# Sheet1.net
KiCad netlist of a schematic drawn in Altium Designer
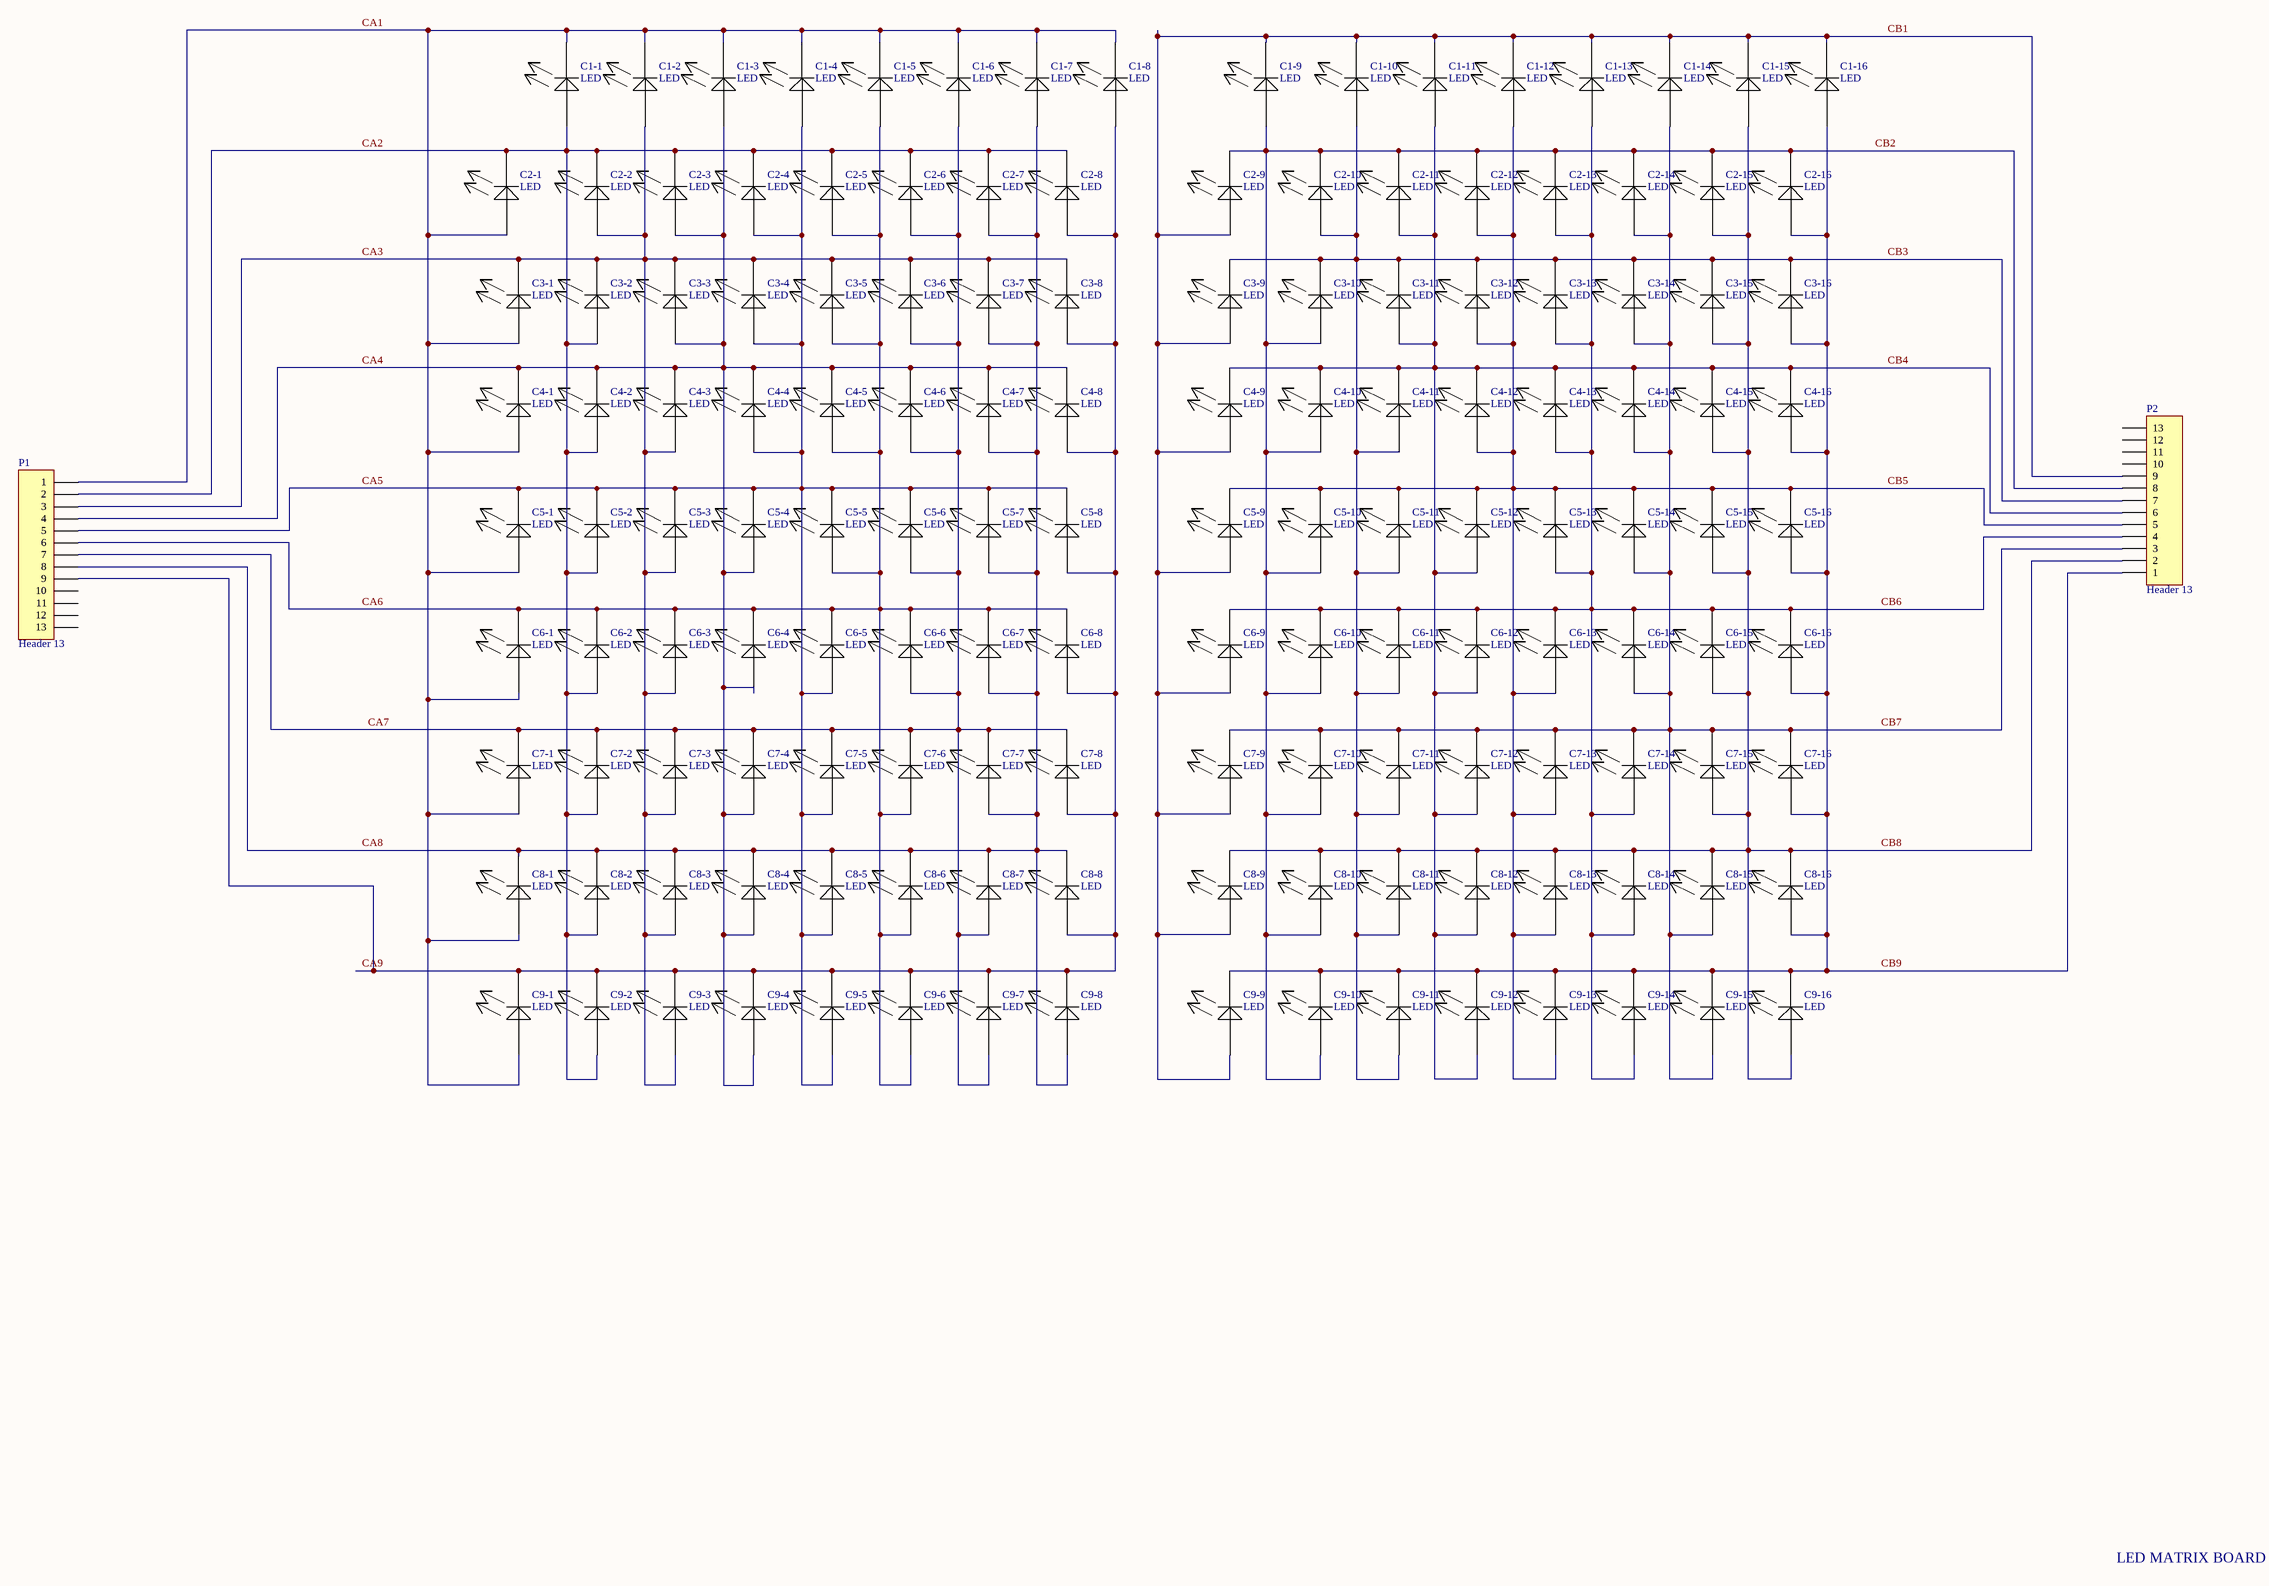
[diagram p0: Sheet1.SchDoc]

(export (version "E")
  (design (tool "Eeschema 10.0.6"))
  (components
    (comp (ref "C1-1") (value "LED") (footprint "LED 0603(2)") (libsource (lib "LEDs") (part "LED")))
    (comp (ref "C1-2") (value "LED") (footprint "LED 0603(2)") (libsource (lib "LEDs") (part "LED")))
    (comp (ref "C1-3") (value "LED") (footprint "LED 0603(2)") (libsource (lib "LEDs") (part "LED")))
    (comp (ref "C1-4") (value "LED") (footprint "LED 0603(2)") (libsource (lib "LEDs") (part "LED")))
    (comp (ref "C1-5") (value "LED") (footprint "LED 0603(2)") (libsource (lib "LEDs") (part "LED")))
    (comp (ref "C1-6") (value "LED") (footprint "LED 0603(2)") (libsource (lib "LEDs") (part "LED")))
    (comp (ref "C1-7") (value "LED") (footprint "LED 0603(2)") (libsource (lib "LEDs") (part "LED")))
    (comp (ref "C1-8") (value "LED") (footprint "LED 0603(2)") (libsource (lib "LEDs") (part "LED")))
    (comp (ref "C1-9") (value "LED") (footprint "LED 0603(2)") (libsource (lib "LEDs") (part "LED")))
    (comp (ref "C1-10") (value "LED") (footprint "LED 0603(2)") (libsource (lib "LEDs") (part "LED")))
    (comp (ref "C1-11") (value "LED") (footprint "LED 0603(2)") (libsource (lib "LEDs") (part "LED")))
    (comp (ref "C1-12") (value "LED") (footprint "LED 0603(2)") (libsource (lib "LEDs") (part "LED")))
    (comp (ref "C1-13") (value "LED") (footprint "LED 0603(2)") (libsource (lib "LEDs") (part "LED")))
    (comp (ref "C1-14") (value "LED") (footprint "LED 0603(2)") (libsource (lib "LEDs") (part "LED")))
    (comp (ref "C1-15") (value "LED") (footprint "LED 0603(2)") (libsource (lib "LEDs") (part "LED")))
    (comp (ref "C1-16") (value "LED") (footprint "LED 0603(2)") (libsource (lib "LEDs") (part "LED")))
    (comp (ref "C2-1") (value "LED") (footprint "LED 0603(2)") (libsource (lib "LEDs") (part "LED")))
    (comp (ref "C2-2") (value "LED") (footprint "LED 0603(2)") (libsource (lib "LEDs") (part "LED")))
    (comp (ref "C2-3") (value "LED") (footprint "LED 0603(2)") (libsource (lib "LEDs") (part "LED")))
    (comp (ref "C2-4") (value "LED") (footprint "LED 0603(2)") (libsource (lib "LEDs") (part "LED")))
    (comp (ref "C2-5") (value "LED") (footprint "LED 0603(2)") (libsource (lib "LEDs") (part "LED")))
    (comp (ref "C2-6") (value "LED") (footprint "LED 0603(2)") (libsource (lib "LEDs") (part "LED")))
    (comp (ref "C2-7") (value "LED") (footprint "LED 0603(2)") (libsource (lib "LEDs") (part "LED")))
    (comp (ref "C2-8") (value "LED") (footprint "LED 0603(2)") (libsource (lib "LEDs") (part "LED")))
    (comp (ref "C2-9") (value "LED") (footprint "LED 0603(2)") (libsource (lib "LEDs") (part "LED")))
    (comp (ref "C2-10") (value "LED") (footprint "LED 0603(2)") (libsource (lib "LEDs") (part "LED")))
    (comp (ref "C2-11") (value "LED") (footprint "LED 0603(2)") (libsource (lib "LEDs") (part "LED")))
    (comp (ref "C2-12") (value "LED") (footprint "LED 0603(2)") (libsource (lib "LEDs") (part "LED")))
    (comp (ref "C2-13") (value "LED") (footprint "LED 0603(2)") (libsource (lib "LEDs") (part "LED")))
    (comp (ref "C2-14") (value "LED") (footprint "LED 0603(2)") (libsource (lib "LEDs") (part "LED")))
    (comp (ref "C2-15") (value "LED") (footprint "LED 0603(2)") (libsource (lib "LEDs") (part "LED")))
    (comp (ref "C2-16") (value "LED") (footprint "LED 0603(2)") (libsource (lib "LEDs") (part "LED")))
    (comp (ref "C3-1") (value "LED") (footprint "LED 0603(2)") (libsource (lib "LEDs") (part "LED")))
    (comp (ref "C3-2") (value "LED") (footprint "LED 0603(2)") (libsource (lib "LEDs") (part "LED")))
    (comp (ref "C3-3") (value "LED") (footprint "LED 0603(2)") (libsource (lib "LEDs") (part "LED")))
    (comp (ref "C3-4") (value "LED") (footprint "LED 0603(2)") (libsource (lib "LEDs") (part "LED")))
    (comp (ref "C3-5") (value "LED") (footprint "LED 0603(2)") (libsource (lib "LEDs") (part "LED")))
    (comp (ref "C3-6") (value "LED") (footprint "LED 0603(2)") (libsource (lib "LEDs") (part "LED")))
    (comp (ref "C3-7") (value "LED") (footprint "LED 0603(2)") (libsource (lib "LEDs") (part "LED")))
    (comp (ref "C3-8") (value "LED") (footprint "LED 0603(2)") (libsource (lib "LEDs") (part "LED")))
    (comp (ref "C3-9") (value "LED") (footprint "LED 0603(2)") (libsource (lib "LEDs") (part "LED")))
    (comp (ref "C3-10") (value "LED") (footprint "LED 0603(2)") (libsource (lib "LEDs") (part "LED")))
    (comp (ref "C3-11") (value "LED") (footprint "LED 0603(2)") (libsource (lib "LEDs") (part "LED")))
    (comp (ref "C3-12") (value "LED") (footprint "LED 0603(2)") (libsource (lib "LEDs") (part "LED")))
    (comp (ref "C3-13") (value "LED") (footprint "LED 0603(2)") (libsource (lib "LEDs") (part "LED")))
    (comp (ref "C3-14") (value "LED") (footprint "LED 0603(2)") (libsource (lib "LEDs") (part "LED")))
    (comp (ref "C3-15") (value "LED") (footprint "LED 0603(2)") (libsource (lib "LEDs") (part "LED")))
    (comp (ref "C3-16") (value "LED") (footprint "LED 0603(2)") (libsource (lib "LEDs") (part "LED")))
    (comp (ref "C4-1") (value "LED") (footprint "LED 0603(2)") (libsource (lib "LEDs") (part "LED")))
    (comp (ref "C4-2") (value "LED") (footprint "LED 0603(2)") (libsource (lib "LEDs") (part "LED")))
    (comp (ref "C4-3") (value "LED") (footprint "LED 0603(2)") (libsource (lib "LEDs") (part "LED")))
    (comp (ref "C4-4") (value "LED") (footprint "LED 0603(2)") (libsource (lib "LEDs") (part "LED")))
    (comp (ref "C4-5") (value "LED") (footprint "LED 0603(2)") (libsource (lib "LEDs") (part "LED")))
    (comp (ref "C4-6") (value "LED") (footprint "LED 0603(2)") (libsource (lib "LEDs") (part "LED")))
    (comp (ref "C4-7") (value "LED") (footprint "LED 0603(2)") (libsource (lib "LEDs") (part "LED")))
    (comp (ref "C4-8") (value "LED") (footprint "LED 0603(2)") (libsource (lib "LEDs") (part "LED")))
    (comp (ref "C4-9") (value "LED") (footprint "LED 0603(2)") (libsource (lib "LEDs") (part "LED")))
    (comp (ref "C4-10") (value "LED") (footprint "LED 0603(2)") (libsource (lib "LEDs") (part "LED")))
    (comp (ref "C4-11") (value "LED") (footprint "LED 0603(2)") (libsource (lib "LEDs") (part "LED")))
    (comp (ref "C4-12") (value "LED") (footprint "LED 0603(2)") (libsource (lib "LEDs") (part "LED")))
    (comp (ref "C4-13") (value "LED") (footprint "LED 0603(2)") (libsource (lib "LEDs") (part "LED")))
    (comp (ref "C4-14") (value "LED") (footprint "LED 0603(2)") (libsource (lib "LEDs") (part "LED")))
    (comp (ref "C4-15") (value "LED") (footprint "LED 0603(2)") (libsource (lib "LEDs") (part "LED")))
    (comp (ref "C4-16") (value "LED") (footprint "LED 0603(2)") (libsource (lib "LEDs") (part "LED")))
    (comp (ref "C5-1") (value "LED") (footprint "LED 0603(2)") (libsource (lib "LEDs") (part "LED")))
    (comp (ref "C5-2") (value "LED") (footprint "LED 0603(2)") (libsource (lib "LEDs") (part "LED")))
    (comp (ref "C5-3") (value "LED") (footprint "LED 0603(2)") (libsource (lib "LEDs") (part "LED")))
    (comp (ref "C5-4") (value "LED") (footprint "LED 0603(2)") (libsource (lib "LEDs") (part "LED")))
    (comp (ref "C5-5") (value "LED") (footprint "LED 0603(2)") (libsource (lib "LEDs") (part "LED")))
    (comp (ref "C5-6") (value "LED") (footprint "LED 0603(2)") (libsource (lib "LEDs") (part "LED")))
    (comp (ref "C5-7") (value "LED") (footprint "LED 0603(2)") (libsource (lib "LEDs") (part "LED")))
    (comp (ref "C5-8") (value "LED") (footprint "LED 0603(2)") (libsource (lib "LEDs") (part "LED")))
    (comp (ref "C5-9") (value "LED") (footprint "LED 0603(2)") (libsource (lib "LEDs") (part "LED")))
    (comp (ref "C5-10") (value "LED") (footprint "LED 0603(2)") (libsource (lib "LEDs") (part "LED")))
    (comp (ref "C5-11") (value "LED") (footprint "LED 0603(2)") (libsource (lib "LEDs") (part "LED")))
    (comp (ref "C5-12") (value "LED") (footprint "LED 0603(2)") (libsource (lib "LEDs") (part "LED")))
    (comp (ref "C5-13") (value "LED") (footprint "LED 0603(2)") (libsource (lib "LEDs") (part "LED")))
    (comp (ref "C5-14") (value "LED") (footprint "LED 0603(2)") (libsource (lib "LEDs") (part "LED")))
    (comp (ref "C5-15") (value "LED") (footprint "LED 0603(2)") (libsource (lib "LEDs") (part "LED")))
    (comp (ref "C5-16") (value "LED") (footprint "LED 0603(2)") (libsource (lib "LEDs") (part "LED")))
    (comp (ref "C6-1") (value "LED") (footprint "LED 0603(2)") (libsource (lib "LEDs") (part "LED")))
    (comp (ref "C6-2") (value "LED") (footprint "LED 0603(2)") (libsource (lib "LEDs") (part "LED")))
    (comp (ref "C6-3") (value "LED") (footprint "LED 0603(2)") (libsource (lib "LEDs") (part "LED")))
    (comp (ref "C6-4") (value "LED") (footprint "LED 0603(2)") (libsource (lib "LEDs") (part "LED")))
    (comp (ref "C6-5") (value "LED") (footprint "LED 0603(2)") (libsource (lib "LEDs") (part "LED")))
    (comp (ref "C6-6") (value "LED") (footprint "LED 0603(2)") (libsource (lib "LEDs") (part "LED")))
    (comp (ref "C6-7") (value "LED") (footprint "LED 0603(2)") (libsource (lib "LEDs") (part "LED")))
    (comp (ref "C6-8") (value "LED") (footprint "LED 0603(2)") (libsource (lib "LEDs") (part "LED")))
    (comp (ref "C6-9") (value "LED") (footprint "LED 0603(2)") (libsource (lib "LEDs") (part "LED")))
    (comp (ref "C6-10") (value "LED") (footprint "LED 0603(2)") (libsource (lib "LEDs") (part "LED")))
    (comp (ref "C6-11") (value "LED") (footprint "LED 0603(2)") (libsource (lib "LEDs") (part "LED")))
    (comp (ref "C6-12") (value "LED") (footprint "LED 0603(2)") (libsource (lib "LEDs") (part "LED")))
    (comp (ref "C6-13") (value "LED") (footprint "LED 0603(2)") (libsource (lib "LEDs") (part "LED")))
    (comp (ref "C6-14") (value "LED") (footprint "LED 0603(2)") (libsource (lib "LEDs") (part "LED")))
    (comp (ref "C6-15") (value "LED") (footprint "LED 0603(2)") (libsource (lib "LEDs") (part "LED")))
    (comp (ref "C6-16") (value "LED") (footprint "LED 0603(2)") (libsource (lib "LEDs") (part "LED")))
    (comp (ref "C7-1") (value "LED") (footprint "LED 0603(2)") (libsource (lib "LEDs") (part "LED")))
    (comp (ref "C7-2") (value "LED") (footprint "LED 0603(2)") (libsource (lib "LEDs") (part "LED")))
    (comp (ref "C7-3") (value "LED") (footprint "LED 0603(2)") (libsource (lib "LEDs") (part "LED")))
    (comp (ref "C7-4") (value "LED") (footprint "LED 0603(2)") (libsource (lib "LEDs") (part "LED")))
    (comp (ref "C7-5") (value "LED") (footprint "LED 0603(2)") (libsource (lib "LEDs") (part "LED")))
    (comp (ref "C7-6") (value "LED") (footprint "LED 0603(2)") (libsource (lib "LEDs") (part "LED")))
    (comp (ref "C7-7") (value "LED") (footprint "LED 0603(2)") (libsource (lib "LEDs") (part "LED")))
    (comp (ref "C7-8") (value "LED") (footprint "LED 0603(2)") (libsource (lib "LEDs") (part "LED")))
    (comp (ref "C7-9") (value "LED") (footprint "LED 0603(2)") (libsource (lib "LEDs") (part "LED")))
    (comp (ref "C7-10") (value "LED") (footprint "LED 0603(2)") (libsource (lib "LEDs") (part "LED")))
    (comp (ref "C7-11") (value "LED") (footprint "LED 0603(2)") (libsource (lib "LEDs") (part "LED")))
    (comp (ref "C7-12") (value "LED") (footprint "LED 0603(2)") (libsource (lib "LEDs") (part "LED")))
    (comp (ref "C7-13") (value "LED") (footprint "LED 0603(2)") (libsource (lib "LEDs") (part "LED")))
    (comp (ref "C7-14") (value "LED") (footprint "LED 0603(2)") (libsource (lib "LEDs") (part "LED")))
    (comp (ref "C7-15") (value "LED") (footprint "LED 0603(2)") (libsource (lib "LEDs") (part "LED")))
    (comp (ref "C7-16") (value "LED") (footprint "LED 0603(2)") (libsource (lib "LEDs") (part "LED")))
    (comp (ref "C8-1") (value "LED") (footprint "LED 0603(2)") (libsource (lib "LEDs") (part "LED")))
    (comp (ref "C8-2") (value "LED") (footprint "LED 0603(2)") (libsource (lib "LEDs") (part "LED")))
    (comp (ref "C8-3") (value "LED") (footprint "LED 0603(2)") (libsource (lib "LEDs") (part "LED")))
    (comp (ref "C8-4") (value "LED") (footprint "LED 0603(2)") (libsource (lib "LEDs") (part "LED")))
    (comp (ref "C8-5") (value "LED") (footprint "LED 0603(2)") (libsource (lib "LEDs") (part "LED")))
    (comp (ref "C8-6") (value "LED") (footprint "LED 0603(2)") (libsource (lib "LEDs") (part "LED")))
    (comp (ref "C8-7") (value "LED") (footprint "LED 0603(2)") (libsource (lib "LEDs") (part "LED")))
    (comp (ref "C8-8") (value "LED") (footprint "LED 0603(2)") (libsource (lib "LEDs") (part "LED")))
    (comp (ref "C8-9") (value "LED") (footprint "LED 0603(2)") (libsource (lib "LEDs") (part "LED")))
    (comp (ref "C8-10") (value "LED") (footprint "LED 0603(2)") (libsource (lib "LEDs") (part "LED")))
    (comp (ref "C8-11") (value "LED") (footprint "LED 0603(2)") (libsource (lib "LEDs") (part "LED")))
    (comp (ref "C8-12") (value "LED") (footprint "LED 0603(2)") (libsource (lib "LEDs") (part "LED")))
    (comp (ref "C8-13") (value "LED") (footprint "LED 0603(2)") (libsource (lib "LEDs") (part "LED")))
    (comp (ref "C8-14") (value "LED") (footprint "LED 0603(2)") (libsource (lib "LEDs") (part "LED")))
    (comp (ref "C8-15") (value "LED") (footprint "LED 0603(2)") (libsource (lib "LEDs") (part "LED")))
    (comp (ref "C8-16") (value "LED") (footprint "LED 0603(2)") (libsource (lib "LEDs") (part "LED")))
    (comp (ref "C9-1") (value "LED") (footprint "LED 0603(2)") (libsource (lib "LEDs") (part "LED")))
    (comp (ref "C9-2") (value "LED") (footprint "LED 0603(2)") (libsource (lib "LEDs") (part "LED")))
    (comp (ref "C9-3") (value "LED") (footprint "LED 0603(2)") (libsource (lib "LEDs") (part "LED")))
    (comp (ref "C9-4") (value "LED") (footprint "LED 0603(2)") (libsource (lib "LEDs") (part "LED")))
    (comp (ref "C9-5") (value "LED") (footprint "LED 0603(2)") (libsource (lib "LEDs") (part "LED")))
    (comp (ref "C9-6") (value "LED") (footprint "LED 0603(2)") (libsource (lib "LEDs") (part "LED")))
    (comp (ref "C9-7") (value "LED") (footprint "LED 0603(2)") (libsource (lib "LEDs") (part "LED")))
    (comp (ref "C9-8") (value "LED") (footprint "LED 0603(2)") (libsource (lib "LEDs") (part "LED")))
    (comp (ref "C9-9") (value "LED") (footprint "LED 0603(2)") (libsource (lib "LEDs") (part "LED")))
    (comp (ref "C9-10") (value "LED") (footprint "LED 0603(2)") (libsource (lib "LEDs") (part "LED")))
    (comp (ref "C9-11") (value "LED") (footprint "LED 0603(2)") (libsource (lib "LEDs") (part "LED")))
    (comp (ref "C9-12") (value "LED") (footprint "LED 0603(2)") (libsource (lib "LEDs") (part "LED")))
    (comp (ref "C9-13") (value "LED") (footprint "LED 0603(2)") (libsource (lib "LEDs") (part "LED")))
    (comp (ref "C9-14") (value "LED") (footprint "LED 0603(2)") (libsource (lib "LEDs") (part "LED")))
    (comp (ref "C9-15") (value "LED") (footprint "LED 0603(2)") (libsource (lib "LEDs") (part "LED")))
    (comp (ref "C9-16") (value "LED") (footprint "LED 0603(2)") (libsource (lib "LEDs") (part "LED")))
    (comp (ref "P1")
      (value "Header 13")
      (footprint "HDR1X13")
      (description "Header, 13-Pin")
      (fields (field (name "PUBLISHER") "Altium Limited"))
      (libsource (lib "Miscellaneous Connectors") (part "Header 13"))
    )
    (comp (ref "P2")
      (value "Header 13")
      (footprint "HDR1X13")
      (description "Header, 13-Pin")
      (fields (field (name "PUBLISHER") "Altium Limited"))
      (libsource (lib "") (part "Header 13_1"))
    )
  )
  (nets
    (net (code "1") (name "/CA1") (class "Default")
      (node (ref "C1-1") (pin "2") (pinfunction "-_2") (pintype "passive"))
      (node (ref "C1-2") (pin "2") (pinfunction "-_2") (pintype "passive"))
      (node (ref "C1-3") (pin "2") (pinfunction "-_2") (pintype "passive"))
      (node (ref "C1-4") (pin "2") (pinfunction "-_2") (pintype "passive"))
      (node (ref "C1-5") (pin "2") (pinfunction "-_2") (pintype "passive"))
      (node (ref "C1-6") (pin "2") (pinfunction "-_2") (pintype "passive"))
      (node (ref "C1-7") (pin "2") (pinfunction "-_2") (pintype "passive"))
      (node (ref "C1-8") (pin "2") (pinfunction "-_2") (pintype "passive"))
      (node (ref "C2-1") (pin "1") (pinfunction "+_1") (pintype "passive"))
      (node (ref "C3-1") (pin "1") (pinfunction "+_1") (pintype "passive"))
      (node (ref "C4-1") (pin "1") (pinfunction "+_1") (pintype "passive"))
      (node (ref "C5-1") (pin "1") (pinfunction "+_1") (pintype "passive"))
      (node (ref "C6-1") (pin "1") (pinfunction "+_1") (pintype "passive"))
      (node (ref "C7-1") (pin "1") (pinfunction "+_1") (pintype "passive"))
      (node (ref "C8-1") (pin "1") (pinfunction "+_1") (pintype "passive"))
      (node (ref "C9-1") (pin "1") (pinfunction "+_1") (pintype "passive"))
      (node (ref "P1") (pin "1") (pinfunction "1_1") (pintype "passive"))
    )
    (net (code "2") (name "/CA2") (class "Default")
      (node (ref "C1-1") (pin "1") (pinfunction "+_1") (pintype "passive"))
      (node (ref "C2-1") (pin "2") (pinfunction "-_2") (pintype "passive"))
      (node (ref "C2-2") (pin "2") (pinfunction "-_2") (pintype "passive"))
      (node (ref "C2-3") (pin "2") (pinfunction "-_2") (pintype "passive"))
      (node (ref "C2-4") (pin "2") (pinfunction "-_2") (pintype "passive"))
      (node (ref "C2-5") (pin "2") (pinfunction "-_2") (pintype "passive"))
      (node (ref "C2-6") (pin "2") (pinfunction "-_2") (pintype "passive"))
      (node (ref "C2-7") (pin "2") (pinfunction "-_2") (pintype "passive"))
      (node (ref "C2-8") (pin "2") (pinfunction "-_2") (pintype "passive"))
      (node (ref "C3-2") (pin "1") (pinfunction "+_1") (pintype "passive"))
      (node (ref "C4-2") (pin "1") (pinfunction "+_1") (pintype "passive"))
      (node (ref "C5-2") (pin "1") (pinfunction "+_1") (pintype "passive"))
      (node (ref "C6-2") (pin "1") (pinfunction "+_1") (pintype "passive"))
      (node (ref "C7-2") (pin "1") (pinfunction "+_1") (pintype "passive"))
      (node (ref "C8-2") (pin "1") (pinfunction "+_1") (pintype "passive"))
      (node (ref "C9-2") (pin "1") (pinfunction "+_1") (pintype "passive"))
      (node (ref "P1") (pin "2") (pinfunction "2_2") (pintype "passive"))
    )
    (net (code "3") (name "/CA3") (class "Default")
      (node (ref "C1-2") (pin "1") (pinfunction "+_1") (pintype "passive"))
      (node (ref "C2-2") (pin "1") (pinfunction "+_1") (pintype "passive"))
      (node (ref "C3-1") (pin "2") (pinfunction "-_2") (pintype "passive"))
      (node (ref "C3-2") (pin "2") (pinfunction "-_2") (pintype "passive"))
      (node (ref "C3-3") (pin "2") (pinfunction "-_2") (pintype "passive"))
      (node (ref "C3-4") (pin "2") (pinfunction "-_2") (pintype "passive"))
      (node (ref "C3-5") (pin "2") (pinfunction "-_2") (pintype "passive"))
      (node (ref "C3-6") (pin "2") (pinfunction "-_2") (pintype "passive"))
      (node (ref "C3-7") (pin "2") (pinfunction "-_2") (pintype "passive"))
      (node (ref "C3-8") (pin "2") (pinfunction "-_2") (pintype "passive"))
      (node (ref "C4-3") (pin "1") (pinfunction "+_1") (pintype "passive"))
      (node (ref "C5-3") (pin "1") (pinfunction "+_1") (pintype "passive"))
      (node (ref "C6-3") (pin "1") (pinfunction "+_1") (pintype "passive"))
      (node (ref "C7-3") (pin "1") (pinfunction "+_1") (pintype "passive"))
      (node (ref "C8-3") (pin "1") (pinfunction "+_1") (pintype "passive"))
      (node (ref "C9-3") (pin "1") (pinfunction "+_1") (pintype "passive"))
      (node (ref "P1") (pin "3") (pinfunction "3_3") (pintype "passive"))
    )
    (net (code "4") (name "/CA4") (class "Default")
      (node (ref "C1-3") (pin "1") (pinfunction "+_1") (pintype "passive"))
      (node (ref "C2-3") (pin "1") (pinfunction "+_1") (pintype "passive"))
      (node (ref "C3-3") (pin "1") (pinfunction "+_1") (pintype "passive"))
      (node (ref "C4-1") (pin "2") (pinfunction "-_2") (pintype "passive"))
      (node (ref "C4-2") (pin "2") (pinfunction "-_2") (pintype "passive"))
      (node (ref "C4-3") (pin "2") (pinfunction "-_2") (pintype "passive"))
      (node (ref "C4-4") (pin "2") (pinfunction "-_2") (pintype "passive"))
      (node (ref "C4-5") (pin "2") (pinfunction "-_2") (pintype "passive"))
      (node (ref "C4-6") (pin "2") (pinfunction "-_2") (pintype "passive"))
      (node (ref "C4-7") (pin "2") (pinfunction "-_2") (pintype "passive"))
      (node (ref "C4-8") (pin "2") (pinfunction "-_2") (pintype "passive"))
      (node (ref "C5-4") (pin "1") (pinfunction "+_1") (pintype "passive"))
      (node (ref "C6-4") (pin "1") (pinfunction "+_1") (pintype "passive"))
      (node (ref "C7-4") (pin "1") (pinfunction "+_1") (pintype "passive"))
      (node (ref "C8-4") (pin "1") (pinfunction "+_1") (pintype "passive"))
      (node (ref "C9-4") (pin "1") (pinfunction "+_1") (pintype "passive"))
      (node (ref "P1") (pin "4") (pinfunction "4_4") (pintype "passive"))
    )
    (net (code "5") (name "/CA5") (class "Default")
      (node (ref "C1-4") (pin "1") (pinfunction "+_1") (pintype "passive"))
      (node (ref "C2-4") (pin "1") (pinfunction "+_1") (pintype "passive"))
      (node (ref "C3-4") (pin "1") (pinfunction "+_1") (pintype "passive"))
      (node (ref "C4-4") (pin "1") (pinfunction "+_1") (pintype "passive"))
      (node (ref "C5-1") (pin "2") (pinfunction "-_2") (pintype "passive"))
      (node (ref "C5-2") (pin "2") (pinfunction "-_2") (pintype "passive"))
      (node (ref "C5-3") (pin "2") (pinfunction "-_2") (pintype "passive"))
      (node (ref "C5-4") (pin "2") (pinfunction "-_2") (pintype "passive"))
      (node (ref "C5-5") (pin "2") (pinfunction "-_2") (pintype "passive"))
      (node (ref "C5-6") (pin "2") (pinfunction "-_2") (pintype "passive"))
      (node (ref "C5-7") (pin "2") (pinfunction "-_2") (pintype "passive"))
      (node (ref "C5-8") (pin "2") (pinfunction "-_2") (pintype "passive"))
      (node (ref "C6-5") (pin "1") (pinfunction "+_1") (pintype "passive"))
      (node (ref "C7-5") (pin "1") (pinfunction "+_1") (pintype "passive"))
      (node (ref "C8-5") (pin "1") (pinfunction "+_1") (pintype "passive"))
      (node (ref "C9-5") (pin "1") (pinfunction "+_1") (pintype "passive"))
      (node (ref "P1") (pin "5") (pinfunction "5_5") (pintype "passive"))
    )
    (net (code "6") (name "/CA6") (class "Default")
      (node (ref "C1-5") (pin "1") (pinfunction "+_1") (pintype "passive"))
      (node (ref "C2-5") (pin "1") (pinfunction "+_1") (pintype "passive"))
      (node (ref "C3-5") (pin "1") (pinfunction "+_1") (pintype "passive"))
      (node (ref "C4-5") (pin "1") (pinfunction "+_1") (pintype "passive"))
      (node (ref "C5-5") (pin "1") (pinfunction "+_1") (pintype "passive"))
      (node (ref "C6-1") (pin "2") (pinfunction "-_2") (pintype "passive"))
      (node (ref "C6-2") (pin "2") (pinfunction "-_2") (pintype "passive"))
      (node (ref "C6-3") (pin "2") (pinfunction "-_2") (pintype "passive"))
      (node (ref "C6-4") (pin "2") (pinfunction "-_2") (pintype "passive"))
      (node (ref "C6-5") (pin "2") (pinfunction "-_2") (pintype "passive"))
      (node (ref "C6-6") (pin "2") (pinfunction "-_2") (pintype "passive"))
      (node (ref "C6-7") (pin "2") (pinfunction "-_2") (pintype "passive"))
      (node (ref "C6-8") (pin "2") (pinfunction "-_2") (pintype "passive"))
      (node (ref "C7-6") (pin "1") (pinfunction "+_1") (pintype "passive"))
      (node (ref "C8-6") (pin "1") (pinfunction "+_1") (pintype "passive"))
      (node (ref "C9-6") (pin "1") (pinfunction "+_1") (pintype "passive"))
      (node (ref "P1") (pin "6") (pinfunction "6_6") (pintype "passive"))
    )
    (net (code "7") (name "/CA7") (class "Default")
      (node (ref "C1-6") (pin "1") (pinfunction "+_1") (pintype "passive"))
      (node (ref "C2-6") (pin "1") (pinfunction "+_1") (pintype "passive"))
      (node (ref "C3-6") (pin "1") (pinfunction "+_1") (pintype "passive"))
      (node (ref "C4-6") (pin "1") (pinfunction "+_1") (pintype "passive"))
      (node (ref "C5-6") (pin "1") (pinfunction "+_1") (pintype "passive"))
      (node (ref "C6-6") (pin "1") (pinfunction "+_1") (pintype "passive"))
      (node (ref "C7-1") (pin "2") (pinfunction "-_2") (pintype "passive"))
      (node (ref "C7-2") (pin "2") (pinfunction "-_2") (pintype "passive"))
      (node (ref "C7-3") (pin "2") (pinfunction "-_2") (pintype "passive"))
      (node (ref "C7-4") (pin "2") (pinfunction "-_2") (pintype "passive"))
      (node (ref "C7-5") (pin "2") (pinfunction "-_2") (pintype "passive"))
      (node (ref "C7-6") (pin "2") (pinfunction "-_2") (pintype "passive"))
      (node (ref "C7-7") (pin "2") (pinfunction "-_2") (pintype "passive"))
      (node (ref "C7-8") (pin "2") (pinfunction "-_2") (pintype "passive"))
      (node (ref "C8-7") (pin "1") (pinfunction "+_1") (pintype "passive"))
      (node (ref "C9-7") (pin "1") (pinfunction "+_1") (pintype "passive"))
      (node (ref "P1") (pin "7") (pinfunction "7_7") (pintype "passive"))
    )
    (net (code "8") (name "/CA8") (class "Default")
      (node (ref "C1-7") (pin "1") (pinfunction "+_1") (pintype "passive"))
      (node (ref "C2-7") (pin "1") (pinfunction "+_1") (pintype "passive"))
      (node (ref "C3-7") (pin "1") (pinfunction "+_1") (pintype "passive"))
      (node (ref "C4-7") (pin "1") (pinfunction "+_1") (pintype "passive"))
      (node (ref "C5-7") (pin "1") (pinfunction "+_1") (pintype "passive"))
      (node (ref "C6-7") (pin "1") (pinfunction "+_1") (pintype "passive"))
      (node (ref "C7-7") (pin "1") (pinfunction "+_1") (pintype "passive"))
      (node (ref "C8-1") (pin "2") (pinfunction "-_2") (pintype "passive"))
      (node (ref "C8-2") (pin "2") (pinfunction "-_2") (pintype "passive"))
      (node (ref "C8-3") (pin "2") (pinfunction "-_2") (pintype "passive"))
      (node (ref "C8-4") (pin "2") (pinfunction "-_2") (pintype "passive"))
      (node (ref "C8-5") (pin "2") (pinfunction "-_2") (pintype "passive"))
      (node (ref "C8-6") (pin "2") (pinfunction "-_2") (pintype "passive"))
      (node (ref "C8-7") (pin "2") (pinfunction "-_2") (pintype "passive"))
      (node (ref "C8-8") (pin "2") (pinfunction "-_2") (pintype "passive"))
      (node (ref "C9-8") (pin "1") (pinfunction "+_1") (pintype "passive"))
      (node (ref "P1") (pin "8") (pinfunction "8_8") (pintype "passive"))
    )
    (net (code "9") (name "/CA9") (class "Default")
      (node (ref "C1-8") (pin "1") (pinfunction "+_1") (pintype "passive"))
      (node (ref "C2-8") (pin "1") (pinfunction "+_1") (pintype "passive"))
      (node (ref "C3-8") (pin "1") (pinfunction "+_1") (pintype "passive"))
      (node (ref "C4-8") (pin "1") (pinfunction "+_1") (pintype "passive"))
      (node (ref "C5-8") (pin "1") (pinfunction "+_1") (pintype "passive"))
      (node (ref "C6-8") (pin "1") (pinfunction "+_1") (pintype "passive"))
      (node (ref "C7-8") (pin "1") (pinfunction "+_1") (pintype "passive"))
      (node (ref "C8-8") (pin "1") (pinfunction "+_1") (pintype "passive"))
      (node (ref "C9-1") (pin "2") (pinfunction "-_2") (pintype "passive"))
      (node (ref "C9-2") (pin "2") (pinfunction "-_2") (pintype "passive"))
      (node (ref "C9-3") (pin "2") (pinfunction "-_2") (pintype "passive"))
      (node (ref "C9-4") (pin "2") (pinfunction "-_2") (pintype "passive"))
      (node (ref "C9-5") (pin "2") (pinfunction "-_2") (pintype "passive"))
      (node (ref "C9-6") (pin "2") (pinfunction "-_2") (pintype "passive"))
      (node (ref "C9-7") (pin "2") (pinfunction "-_2") (pintype "passive"))
      (node (ref "C9-8") (pin "2") (pinfunction "-_2") (pintype "passive"))
      (node (ref "P1") (pin "9") (pinfunction "9_9") (pintype "passive"))
    )
    (net (code "10") (name "/CB1") (class "Default")
      (node (ref "C1-10") (pin "2") (pinfunction "-_2") (pintype "passive"))
      (node (ref "C1-11") (pin "2") (pinfunction "-_2") (pintype "passive"))
      (node (ref "C1-12") (pin "2") (pinfunction "-_2") (pintype "passive"))
      (node (ref "C1-13") (pin "2") (pinfunction "-_2") (pintype "passive"))
      (node (ref "C1-14") (pin "2") (pinfunction "-_2") (pintype "passive"))
      (node (ref "C1-15") (pin "2") (pinfunction "-_2") (pintype "passive"))
      (node (ref "C1-16") (pin "2") (pinfunction "-_2") (pintype "passive"))
      (node (ref "C1-9") (pin "2") (pinfunction "-_2") (pintype "passive"))
      (node (ref "C2-9") (pin "1") (pinfunction "+_1") (pintype "passive"))
      (node (ref "C3-9") (pin "1") (pinfunction "+_1") (pintype "passive"))
      (node (ref "C4-9") (pin "1") (pinfunction "+_1") (pintype "passive"))
      (node (ref "C5-9") (pin "1") (pinfunction "+_1") (pintype "passive"))
      (node (ref "C6-9") (pin "1") (pinfunction "+_1") (pintype "passive"))
      (node (ref "C7-9") (pin "1") (pinfunction "+_1") (pintype "passive"))
      (node (ref "C8-9") (pin "1") (pinfunction "+_1") (pintype "passive"))
      (node (ref "C9-9") (pin "1") (pinfunction "+_1") (pintype "passive"))
      (node (ref "P2") (pin "9") (pinfunction "9_9") (pintype "passive"))
    )
    (net (code "11") (name "/CB2") (class "Default")
      (node (ref "C1-9") (pin "1") (pinfunction "+_1") (pintype "passive"))
      (node (ref "C2-10") (pin "2") (pinfunction "-_2") (pintype "passive"))
      (node (ref "C2-11") (pin "2") (pinfunction "-_2") (pintype "passive"))
      (node (ref "C2-12") (pin "2") (pinfunction "-_2") (pintype "passive"))
      (node (ref "C2-13") (pin "2") (pinfunction "-_2") (pintype "passive"))
      (node (ref "C2-14") (pin "2") (pinfunction "-_2") (pintype "passive"))
      (node (ref "C2-15") (pin "2") (pinfunction "-_2") (pintype "passive"))
      (node (ref "C2-16") (pin "2") (pinfunction "-_2") (pintype "passive"))
      (node (ref "C2-9") (pin "2") (pinfunction "-_2") (pintype "passive"))
      (node (ref "C3-10") (pin "1") (pinfunction "+_1") (pintype "passive"))
      (node (ref "C4-10") (pin "1") (pinfunction "+_1") (pintype "passive"))
      (node (ref "C5-10") (pin "1") (pinfunction "+_1") (pintype "passive"))
      (node (ref "C6-10") (pin "1") (pinfunction "+_1") (pintype "passive"))
      (node (ref "C7-10") (pin "1") (pinfunction "+_1") (pintype "passive"))
      (node (ref "C8-10") (pin "1") (pinfunction "+_1") (pintype "passive"))
      (node (ref "C9-10") (pin "1") (pinfunction "+_1") (pintype "passive"))
      (node (ref "P2") (pin "8") (pinfunction "8_8") (pintype "passive"))
    )
    (net (code "12") (name "/CB3") (class "Default")
      (node (ref "C1-10") (pin "1") (pinfunction "+_1") (pintype "passive"))
      (node (ref "C2-10") (pin "1") (pinfunction "+_1") (pintype "passive"))
      (node (ref "C3-10") (pin "2") (pinfunction "-_2") (pintype "passive"))
      (node (ref "C3-11") (pin "2") (pinfunction "-_2") (pintype "passive"))
      (node (ref "C3-12") (pin "2") (pinfunction "-_2") (pintype "passive"))
      (node (ref "C3-13") (pin "2") (pinfunction "-_2") (pintype "passive"))
      (node (ref "C3-14") (pin "2") (pinfunction "-_2") (pintype "passive"))
      (node (ref "C3-15") (pin "2") (pinfunction "-_2") (pintype "passive"))
      (node (ref "C3-16") (pin "2") (pinfunction "-_2") (pintype "passive"))
      (node (ref "C3-9") (pin "2") (pinfunction "-_2") (pintype "passive"))
      (node (ref "C4-11") (pin "1") (pinfunction "+_1") (pintype "passive"))
      (node (ref "C5-11") (pin "1") (pinfunction "+_1") (pintype "passive"))
      (node (ref "C6-11") (pin "1") (pinfunction "+_1") (pintype "passive"))
      (node (ref "C7-11") (pin "1") (pinfunction "+_1") (pintype "passive"))
      (node (ref "C8-11") (pin "1") (pinfunction "+_1") (pintype "passive"))
      (node (ref "C9-11") (pin "1") (pinfunction "+_1") (pintype "passive"))
      (node (ref "P2") (pin "7") (pinfunction "7_7") (pintype "passive"))
    )
    (net (code "13") (name "/CB4") (class "Default")
      (node (ref "C1-11") (pin "1") (pinfunction "+_1") (pintype "passive"))
      (node (ref "C2-11") (pin "1") (pinfunction "+_1") (pintype "passive"))
      (node (ref "C3-11") (pin "1") (pinfunction "+_1") (pintype "passive"))
      (node (ref "C4-10") (pin "2") (pinfunction "-_2") (pintype "passive"))
      (node (ref "C4-11") (pin "2") (pinfunction "-_2") (pintype "passive"))
      (node (ref "C4-12") (pin "2") (pinfunction "-_2") (pintype "passive"))
      (node (ref "C4-13") (pin "2") (pinfunction "-_2") (pintype "passive"))
      (node (ref "C4-14") (pin "2") (pinfunction "-_2") (pintype "passive"))
      (node (ref "C4-15") (pin "2") (pinfunction "-_2") (pintype "passive"))
      (node (ref "C4-16") (pin "2") (pinfunction "-_2") (pintype "passive"))
      (node (ref "C4-9") (pin "2") (pinfunction "-_2") (pintype "passive"))
      (node (ref "C5-12") (pin "1") (pinfunction "+_1") (pintype "passive"))
      (node (ref "C6-12") (pin "1") (pinfunction "+_1") (pintype "passive"))
      (node (ref "C7-12") (pin "1") (pinfunction "+_1") (pintype "passive"))
      (node (ref "C8-12") (pin "1") (pinfunction "+_1") (pintype "passive"))
      (node (ref "C9-12") (pin "1") (pinfunction "+_1") (pintype "passive"))
      (node (ref "P2") (pin "6") (pinfunction "6_6") (pintype "passive"))
    )
    (net (code "14") (name "/CB5") (class "Default")
      (node (ref "C1-12") (pin "1") (pinfunction "+_1") (pintype "passive"))
      (node (ref "C2-12") (pin "1") (pinfunction "+_1") (pintype "passive"))
      (node (ref "C3-12") (pin "1") (pinfunction "+_1") (pintype "passive"))
      (node (ref "C4-12") (pin "1") (pinfunction "+_1") (pintype "passive"))
      (node (ref "C5-10") (pin "2") (pinfunction "-_2") (pintype "passive"))
      (node (ref "C5-11") (pin "2") (pinfunction "-_2") (pintype "passive"))
      (node (ref "C5-12") (pin "2") (pinfunction "-_2") (pintype "passive"))
      (node (ref "C5-13") (pin "2") (pinfunction "-_2") (pintype "passive"))
      (node (ref "C5-14") (pin "2") (pinfunction "-_2") (pintype "passive"))
      (node (ref "C5-15") (pin "2") (pinfunction "-_2") (pintype "passive"))
      (node (ref "C5-16") (pin "2") (pinfunction "-_2") (pintype "passive"))
      (node (ref "C5-9") (pin "2") (pinfunction "-_2") (pintype "passive"))
      (node (ref "C6-13") (pin "1") (pinfunction "+_1") (pintype "passive"))
      (node (ref "C7-13") (pin "1") (pinfunction "+_1") (pintype "passive"))
      (node (ref "C8-13") (pin "1") (pinfunction "+_1") (pintype "passive"))
      (node (ref "C9-13") (pin "1") (pinfunction "+_1") (pintype "passive"))
      (node (ref "P2") (pin "5") (pinfunction "5_5") (pintype "passive"))
    )
    (net (code "15") (name "/CB6") (class "Default")
      (node (ref "C1-13") (pin "1") (pinfunction "+_1") (pintype "passive"))
      (node (ref "C2-13") (pin "1") (pinfunction "+_1") (pintype "passive"))
      (node (ref "C3-13") (pin "1") (pinfunction "+_1") (pintype "passive"))
      (node (ref "C4-13") (pin "1") (pinfunction "+_1") (pintype "passive"))
      (node (ref "C5-13") (pin "1") (pinfunction "+_1") (pintype "passive"))
      (node (ref "C6-10") (pin "2") (pinfunction "-_2") (pintype "passive"))
      (node (ref "C6-11") (pin "2") (pinfunction "-_2") (pintype "passive"))
      (node (ref "C6-12") (pin "2") (pinfunction "-_2") (pintype "passive"))
      (node (ref "C6-13") (pin "2") (pinfunction "-_2") (pintype "passive"))
      (node (ref "C6-14") (pin "2") (pinfunction "-_2") (pintype "passive"))
      (node (ref "C6-15") (pin "2") (pinfunction "-_2") (pintype "passive"))
      (node (ref "C6-16") (pin "2") (pinfunction "-_2") (pintype "passive"))
      (node (ref "C6-9") (pin "2") (pinfunction "-_2") (pintype "passive"))
      (node (ref "C7-14") (pin "1") (pinfunction "+_1") (pintype "passive"))
      (node (ref "C8-14") (pin "1") (pinfunction "+_1") (pintype "passive"))
      (node (ref "C9-14") (pin "1") (pinfunction "+_1") (pintype "passive"))
      (node (ref "P2") (pin "4") (pinfunction "4_4") (pintype "passive"))
    )
    (net (code "16") (name "/CB7") (class "Default")
      (node (ref "C1-14") (pin "1") (pinfunction "+_1") (pintype "passive"))
      (node (ref "C2-14") (pin "1") (pinfunction "+_1") (pintype "passive"))
      (node (ref "C3-14") (pin "1") (pinfunction "+_1") (pintype "passive"))
      (node (ref "C4-14") (pin "1") (pinfunction "+_1") (pintype "passive"))
      (node (ref "C5-14") (pin "1") (pinfunction "+_1") (pintype "passive"))
      (node (ref "C6-14") (pin "1") (pinfunction "+_1") (pintype "passive"))
      (node (ref "C7-10") (pin "2") (pinfunction "-_2") (pintype "passive"))
      (node (ref "C7-11") (pin "2") (pinfunction "-_2") (pintype "passive"))
      (node (ref "C7-12") (pin "2") (pinfunction "-_2") (pintype "passive"))
      (node (ref "C7-13") (pin "2") (pinfunction "-_2") (pintype "passive"))
      (node (ref "C7-14") (pin "2") (pinfunction "-_2") (pintype "passive"))
      (node (ref "C7-15") (pin "2") (pinfunction "-_2") (pintype "passive"))
      (node (ref "C7-16") (pin "2") (pinfunction "-_2") (pintype "passive"))
      (node (ref "C7-9") (pin "2") (pinfunction "-_2") (pintype "passive"))
      (node (ref "C8-15") (pin "1") (pinfunction "+_1") (pintype "passive"))
      (node (ref "C9-15") (pin "1") (pinfunction "+_1") (pintype "passive"))
      (node (ref "P2") (pin "3") (pinfunction "3_3") (pintype "passive"))
    )
    (net (code "17") (name "/CB8") (class "Default")
      (node (ref "C1-15") (pin "1") (pinfunction "+_1") (pintype "passive"))
      (node (ref "C2-15") (pin "1") (pinfunction "+_1") (pintype "passive"))
      (node (ref "C3-15") (pin "1") (pinfunction "+_1") (pintype "passive"))
      (node (ref "C4-15") (pin "1") (pinfunction "+_1") (pintype "passive"))
      (node (ref "C5-15") (pin "1") (pinfunction "+_1") (pintype "passive"))
      (node (ref "C6-15") (pin "1") (pinfunction "+_1") (pintype "passive"))
      (node (ref "C7-15") (pin "1") (pinfunction "+_1") (pintype "passive"))
      (node (ref "C8-10") (pin "2") (pinfunction "-_2") (pintype "passive"))
      (node (ref "C8-11") (pin "2") (pinfunction "-_2") (pintype "passive"))
      (node (ref "C8-12") (pin "2") (pinfunction "-_2") (pintype "passive"))
      (node (ref "C8-13") (pin "2") (pinfunction "-_2") (pintype "passive"))
      (node (ref "C8-14") (pin "2") (pinfunction "-_2") (pintype "passive"))
      (node (ref "C8-15") (pin "2") (pinfunction "-_2") (pintype "passive"))
      (node (ref "C8-16") (pin "2") (pinfunction "-_2") (pintype "passive"))
      (node (ref "C8-9") (pin "2") (pinfunction "-_2") (pintype "passive"))
      (node (ref "C9-16") (pin "1") (pinfunction "+_1") (pintype "passive"))
      (node (ref "P2") (pin "2") (pinfunction "2_2") (pintype "passive"))
    )
    (net (code "18") (name "/CB9") (class "Default")
      (node (ref "C1-16") (pin "1") (pinfunction "+_1") (pintype "passive"))
      (node (ref "C2-16") (pin "1") (pinfunction "+_1") (pintype "passive"))
      (node (ref "C3-16") (pin "1") (pinfunction "+_1") (pintype "passive"))
      (node (ref "C4-16") (pin "1") (pinfunction "+_1") (pintype "passive"))
      (node (ref "C5-16") (pin "1") (pinfunction "+_1") (pintype "passive"))
      (node (ref "C6-16") (pin "1") (pinfunction "+_1") (pintype "passive"))
      (node (ref "C7-16") (pin "1") (pinfunction "+_1") (pintype "passive"))
      (node (ref "C8-16") (pin "1") (pinfunction "+_1") (pintype "passive"))
      (node (ref "C9-10") (pin "2") (pinfunction "-_2") (pintype "passive"))
      (node (ref "C9-11") (pin "2") (pinfunction "-_2") (pintype "passive"))
      (node (ref "C9-12") (pin "2") (pinfunction "-_2") (pintype "passive"))
      (node (ref "C9-13") (pin "2") (pinfunction "-_2") (pintype "passive"))
      (node (ref "C9-14") (pin "2") (pinfunction "-_2") (pintype "passive"))
      (node (ref "C9-15") (pin "2") (pinfunction "-_2") (pintype "passive"))
      (node (ref "C9-16") (pin "2") (pinfunction "-_2") (pintype "passive"))
      (node (ref "C9-9") (pin "2") (pinfunction "-_2") (pintype "passive"))
      (node (ref "P2") (pin "1") (pinfunction "1_1") (pintype "passive"))
    )
    (net (code "19") (name "unconnected-(P1-Pad10)") (class "Default")
      (node (ref "P1") (pin "10") (pinfunction "10_10") (pintype "passive"))
    )
    (net (code "20") (name "unconnected-(P1-Pad11)") (class "Default")
      (node (ref "P1") (pin "11") (pinfunction "11_11") (pintype "passive"))
    )
    (net (code "21") (name "unconnected-(P1-Pad12)") (class "Default")
      (node (ref "P1") (pin "12") (pinfunction "12_12") (pintype "passive"))
    )
    (net (code "22") (name "unconnected-(P1-Pad13)") (class "Default")
      (node (ref "P1") (pin "13") (pinfunction "13_13") (pintype "passive"))
    )
    (net (code "23") (name "unconnected-(P2-Pad10)") (class "Default")
      (node (ref "P2") (pin "10") (pinfunction "10_10") (pintype "passive"))
    )
    (net (code "24") (name "unconnected-(P2-Pad11)") (class "Default")
      (node (ref "P2") (pin "11") (pinfunction "11_11") (pintype "passive"))
    )
    (net (code "25") (name "unconnected-(P2-Pad12)") (class "Default")
      (node (ref "P2") (pin "12") (pinfunction "12_12") (pintype "passive"))
    )
    (net (code "26") (name "unconnected-(P2-Pad13)") (class "Default")
      (node (ref "P2") (pin "13") (pinfunction "13_13") (pintype "passive"))
    )
  )
)
